# POWER_REV2.net
KiCad netlist of a schematic drawn in Altium Designer
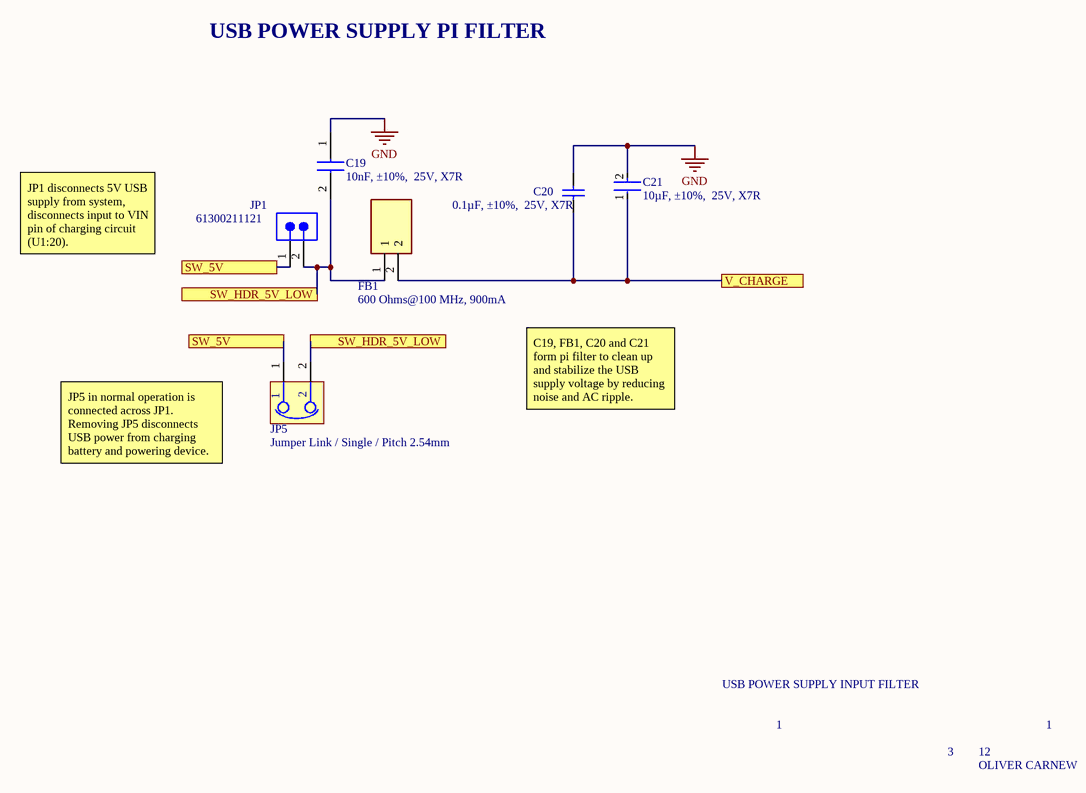
[diagram p0: POWER_REV2.SchDoc]

(export (version "E")
  (design (tool "Eeschema 10.0.6"))
  (components
    (comp (ref "C19")
      (value "10nF, ±10%,  25V, X7R")
      (footprint "SamacSys:C0603")
      (fields
        (field (name "MANUFACTURER_PART_NUMBER") "C0603C103K4RECTU")
        (field (name "MOUSER PART NUMBER") "80-C0603C103K4RECTU")
      )
      (libsource (lib "*") (part "C0603C103K4RECTU"))
    )
    (comp (ref "C20")
      (value "0.1µF, ±10%,  25V, X7R")
      (footprint "CAPC1608X90X35ML10T15")
      (description "Chip Capacitor, 0.1 uF, +/- 10%, 50 V, -55 to 125 degC, 0603 (1608 Metric), RoHS, Tape and Reel")
      (fields (field (name "TOLERANCE") "10%") (field (name "VOLTAGE") "50V"))
      (libsource (lib "Altium Content Vault") (part "CAP-NP-2"))
    )
    (comp (ref "C21")
      (value "10µF, ±10%,  25V, X7R")
      (footprint "FP-CL21B106KOQNNNE-MFG")
      (description "CAP CER 10UF 16V X7R 0805 CL21B106KOQNNNE")
      (fields
        (field (name "MANUFACTURER PART NUMBER") "CL21B106KOQNNNE")
        (field (name "OCTOPART") "https://octopart.com/cl21b106koqnnne-samsung-19832289")
      )
      (libsource (lib "Altium Content Vault") (part "236180d848d6139a670b325ea6854c9"))
    )
    (comp (ref "FB1")
      (value "600 Ohms@100 MHz, 900mA")
      (footprint "SamacSys:BEADC1608X90N")
      (description "600 Ohms @ 100 MHz 1 Power Line Ferrite Bead 0603 (1608 Metric) 900mA 170mOhm")
      (fields
        (field (name "MANUFACTURER_PART_NUMBER") "FBMH1608HM601-T")
        (field (name "MOUSER PART NUMBER") "963-FBMH1608HM601-T")
      )
      (libsource (lib "DANCE_LIB_REV2") (part "FBMH1608HM601-T"))
    )
    (comp (ref "JP1")
      (value "61300211121")
      (footprint "61300211121")
      (libsource (lib "Altium Content Vault") (part "Header_Male_1R_02P"))
    )
    (comp (ref "JP5")
      (value "Jumper Link / Single / Pitch 2.54mm")
      (description "CONNECTOR : PCB Jumper Link / Single / Pitch 2.54mm / Black /shunt.  01-96-02")
      (libsource (lib "DANCE_LIB_REV2") (part "jumper_2.54mm"))
    )
  )
  (nets
    (net (code "1") (name "/SW_5V") (class "Default")
      (node (ref "JP1") (pin "1") (pinfunction "1_1") (pintype "passive"))
      (node (ref "JP5") (pin "1") (pinfunction "1_1") (pintype "passive"))
    )
    (net (code "2") (name "/SW_HDR_5V_LOW") (class "Default")
      (node (ref "C19") (pin "2") (pinfunction "2_2") (pintype "passive"))
      (node (ref "FB1") (pin "1") (pinfunction "1_1") (pintype "passive"))
      (node (ref "JP1") (pin "2") (pinfunction "2_2") (pintype "passive"))
      (node (ref "JP5") (pin "2") (pinfunction "2_2") (pintype "passive"))
    )
    (net (code "3") (name "/V_CHARGE") (class "Default")
      (node (ref "C20") (pin "1") (pinfunction "1_1") (pintype "passive"))
      (node (ref "C21") (pin "1") (pinfunction "1_1") (pintype "passive"))
      (node (ref "FB1") (pin "2") (pinfunction "2_2") (pintype "passive"))
    )
    (net (code "4") (name "GND") (class "Default")
      (node (ref "C19") (pin "1") (pinfunction "1_1") (pintype "passive"))
      (node (ref "C20") (pin "2") (pinfunction "2_2") (pintype "passive"))
      (node (ref "C21") (pin "2") (pinfunction "2_2") (pintype "passive"))
    )
  )
)
